# beamshutter.net
KiCad netlist of a schematic drawn in EAGLE
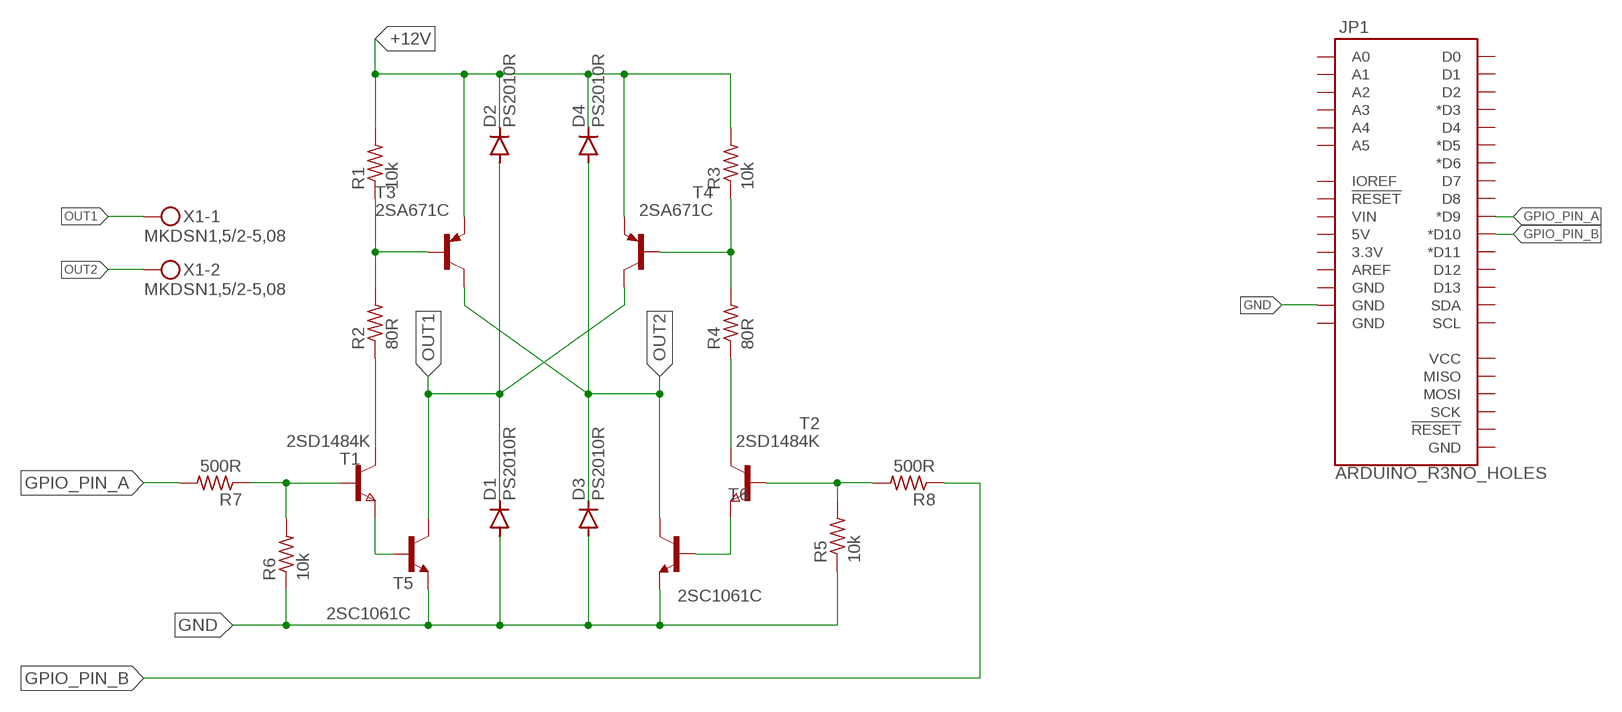
[diagram p0: schematic, sheet 1]

(export (version "E")
  (design (tool "Eeschema 10.0.6"))
  (components
    (comp (ref "D1")
      (value "PS2010R")
      (footprint "eagle-import:DO15-12")
      (libsource (lib "eagle-import") (part "RGP15"))
    )
    (comp (ref "D2")
      (value "PS2010R")
      (footprint "eagle-import:DO15-12")
      (libsource (lib "eagle-import") (part "RGP15"))
    )
    (comp (ref "D3")
      (value "PS2010R")
      (footprint "eagle-import:DO15-12")
      (libsource (lib "eagle-import") (part "RGP15"))
    )
    (comp (ref "D4")
      (value "PS2010R")
      (footprint "eagle-import:DO15-12")
      (libsource (lib "eagle-import") (part "RGP15"))
    )
    (comp (ref "JP1")
      (value "ARDUINO_R3NO_HOLES")
      (footprint "eagle-import:ARDUINO_R3_NO_HOLES")
      (libsource (lib "eagle-import") (part "ARDUINO_R3NO_HOLES"))
    )
    (comp (ref "R1")
      (value "10k")
      (footprint "eagle-import:2012-R")
      (libsource (lib "eagle-import") (part "R-2012"))
    )
    (comp (ref "R2")
      (value "80R")
      (footprint "eagle-import:2012-R")
      (libsource (lib "eagle-import") (part "R-2012"))
    )
    (comp (ref "R3")
      (value "10k")
      (footprint "eagle-import:2012-R")
      (libsource (lib "eagle-import") (part "R-2012"))
    )
    (comp (ref "R4")
      (value "80R")
      (footprint "eagle-import:2012-R")
      (libsource (lib "eagle-import") (part "R-2012"))
    )
    (comp (ref "R5")
      (value "10k")
      (footprint "eagle-import:2012-R")
      (libsource (lib "eagle-import") (part "R-2012"))
    )
    (comp (ref "R6")
      (value "10k")
      (footprint "eagle-import:2012-R")
      (libsource (lib "eagle-import") (part "R-2012"))
    )
    (comp (ref "R7")
      (value "500R")
      (footprint "eagle-import:2012-R")
      (libsource (lib "eagle-import") (part "R-2012"))
    )
    (comp (ref "R8")
      (value "500R")
      (footprint "eagle-import:2012-R")
      (libsource (lib "eagle-import") (part "R-2012"))
    )
    (comp (ref "T1")
      (value "2SD1484K")
      (footprint "eagle-import:SOT323")
      (fields (field (name "MPN") "DSS4160U-7"))
      (libsource (lib "eagle-import") (part "NPNSOT323"))
    )
    (comp (ref "T2")
      (value "2SD1484K")
      (footprint "eagle-import:SOT323")
      (fields (field (name "MPN") "DSS4160U-7"))
      (libsource (lib "eagle-import") (part "NPNSOT323"))
    )
    (comp (ref "T3")
      (value "2SA671C")
      (footprint "eagle-import:TO220V")
      (libsource (lib "eagle-import") (part "-PNP-TO220V"))
    )
    (comp (ref "T4")
      (value "2SA671C")
      (footprint "eagle-import:TO220V")
      (libsource (lib "eagle-import") (part "-PNP-TO220V"))
    )
    (comp (ref "T5")
      (value "2SC1061C")
      (footprint "eagle-import:TO220V")
      (libsource (lib "eagle-import") (part "-NPN-TO220V"))
    )
    (comp (ref "T6")
      (value "2SC1061C")
      (footprint "eagle-import:TO220V")
      (libsource (lib "eagle-import") (part "-NPN-TO220V"))
    )
    (comp (ref "X1")
      (value "MKDSN1,5/2-5,08")
      (footprint "eagle-import:MKDSN1,5_2-5,08")
      (libsource (lib "eagle-import") (part "MKDSN1,5/2-5,08"))
    )
  )
  (nets
    (net (code "1") (name "+12V") (class "Default")
      (node (ref "D2") (pin "C") (pinfunction "C_C") (pintype "passive"))
      (node (ref "D4") (pin "C") (pinfunction "C_C") (pintype "passive"))
      (node (ref "R1") (pin "2") (pinfunction "2_2") (pintype "passive"))
      (node (ref "R3") (pin "2") (pinfunction "2_2") (pintype "passive"))
      (node (ref "T3") (pin "3") (pinfunction "E_3") (pintype "passive"))
      (node (ref "T4") (pin "3") (pinfunction "E_3") (pintype "passive"))
    )
    (net (code "2") (name "GND") (class "Default")
      (node (ref "D1") (pin "A") (pinfunction "A_A") (pintype "passive"))
      (node (ref "D3") (pin "A") (pinfunction "A_A") (pintype "passive"))
      (node (ref "JP1") (pin "GND@3") (pinfunction "GND_GND@3") (pintype "bidirectional"))
      (node (ref "R5") (pin "1") (pinfunction "1_1") (pintype "passive"))
      (node (ref "R6") (pin "1") (pinfunction "1_1") (pintype "passive"))
      (node (ref "T5") (pin "3") (pinfunction "E_3") (pintype "passive"))
      (node (ref "T6") (pin "3") (pinfunction "E_3") (pintype "passive"))
    )
    (net (code "3") (name "GPIO_PIN_A") (class "Default")
      (node (ref "JP1") (pin "D9") (pinfunction "*D9_D9") (pintype "bidirectional"))
      (node (ref "R7") (pin "2") (pinfunction "2_2") (pintype "passive"))
    )
    (net (code "4") (name "GPIO_PIN_B") (class "Default")
      (node (ref "JP1") (pin "D10") (pinfunction "*D10_D10") (pintype "bidirectional"))
      (node (ref "R8") (pin "1") (pinfunction "1_1") (pintype "passive"))
    )
    (net (code "5") (name "Net-(T1-B)") (class "Default")
      (node (ref "R6") (pin "2") (pinfunction "2_2") (pintype "passive"))
      (node (ref "R7") (pin "1") (pinfunction "1_1") (pintype "passive"))
      (node (ref "T1") (pin "2") (pinfunction "B_2") (pintype "passive"))
    )
    (net (code "6") (name "Net-(T1-C)") (class "Default")
      (node (ref "R2") (pin "1") (pinfunction "1_1") (pintype "passive"))
      (node (ref "T1") (pin "1") (pinfunction "C_1") (pintype "passive"))
    )
    (net (code "7") (name "Net-(T1-E)") (class "Default")
      (node (ref "T1") (pin "3") (pinfunction "E_3") (pintype "passive"))
      (node (ref "T5") (pin "1") (pinfunction "B_1") (pintype "passive"))
    )
    (net (code "8") (name "Net-(T2-B)") (class "Default")
      (node (ref "R5") (pin "2") (pinfunction "2_2") (pintype "passive"))
      (node (ref "R8") (pin "2") (pinfunction "2_2") (pintype "passive"))
      (node (ref "T2") (pin "2") (pinfunction "B_2") (pintype "passive"))
    )
    (net (code "9") (name "Net-(T2-C)") (class "Default")
      (node (ref "R4") (pin "1") (pinfunction "1_1") (pintype "passive"))
      (node (ref "T2") (pin "1") (pinfunction "C_1") (pintype "passive"))
    )
    (net (code "10") (name "Net-(T2-E)") (class "Default")
      (node (ref "T2") (pin "3") (pinfunction "E_3") (pintype "passive"))
      (node (ref "T6") (pin "1") (pinfunction "B_1") (pintype "passive"))
    )
    (net (code "11") (name "Net-(T3-B)") (class "Default")
      (node (ref "R1") (pin "1") (pinfunction "1_1") (pintype "passive"))
      (node (ref "R2") (pin "2") (pinfunction "2_2") (pintype "passive"))
      (node (ref "T3") (pin "1") (pinfunction "B_1") (pintype "passive"))
    )
    (net (code "12") (name "Net-(T4-B)") (class "Default")
      (node (ref "R3") (pin "1") (pinfunction "1_1") (pintype "passive"))
      (node (ref "R4") (pin "2") (pinfunction "2_2") (pintype "passive"))
      (node (ref "T4") (pin "1") (pinfunction "B_1") (pintype "passive"))
    )
    (net (code "13") (name "OUT1") (class "Default")
      (node (ref "D1") (pin "C") (pinfunction "C_C") (pintype "passive"))
      (node (ref "D2") (pin "A") (pinfunction "A_A") (pintype "passive"))
      (node (ref "T4") (pin "2") (pinfunction "C_2") (pintype "passive"))
      (node (ref "T5") (pin "2") (pinfunction "C_2") (pintype "passive"))
      (node (ref "X1") (pin "1") (pinfunction "KL_1") (pintype "passive"))
    )
    (net (code "14") (name "OUT2") (class "Default")
      (node (ref "D3") (pin "C") (pinfunction "C_C") (pintype "passive"))
      (node (ref "D4") (pin "A") (pinfunction "A_A") (pintype "passive"))
      (node (ref "T3") (pin "2") (pinfunction "C_2") (pintype "passive"))
      (node (ref "T6") (pin "2") (pinfunction "C_2") (pintype "passive"))
      (node (ref "X1") (pin "2") (pinfunction "KL_2") (pintype "passive"))
    )
    (net (code "15") (name "unconnected-(JP1-*D3-PadD3)") (class "Default")
      (node (ref "JP1") (pin "D3") (pinfunction "*D3_D3") (pintype "bidirectional"))
    )
    (net (code "16") (name "unconnected-(JP1-*D5-PadD5)") (class "Default")
      (node (ref "JP1") (pin "D5") (pinfunction "*D5_D5") (pintype "bidirectional"))
    )
    (net (code "17") (name "unconnected-(JP1-*D6-PadD6)") (class "Default")
      (node (ref "JP1") (pin "D6") (pinfunction "*D6_D6") (pintype "bidirectional"))
    )
    (net (code "18") (name "unconnected-(JP1-*D11-PadD11)") (class "Default")
      (node (ref "JP1") (pin "D11") (pinfunction "*D11_D11") (pintype "bidirectional"))
    )
    (net (code "19") (name "unconnected-(JP1-GND-PadGND@1)") (class "Default")
      (node (ref "JP1") (pin "GND@1") (pinfunction "GND_GND@1") (pintype "bidirectional"))
    )
    (net (code "20") (name "unconnected-(JP1-GND-PadGND@2)") (class "Default")
      (node (ref "JP1") (pin "GND@2") (pinfunction "GND_GND@2") (pintype "bidirectional"))
    )
    (net (code "21") (name "unconnected-(JP1-GND-PadGND@4)") (class "Default")
      (node (ref "JP1") (pin "GND@4") (pinfunction "GND_GND@4") (pintype "bidirectional"))
    )
    (net (code "22") (name "unconnected-(JP1-Pad3.3V)") (class "Default")
      (node (ref "JP1") (pin "3.3V") (pinfunction "3.3V_3.3V") (pintype "bidirectional"))
    )
    (net (code "23") (name "unconnected-(JP1-Pad5V)") (class "Default")
      (node (ref "JP1") (pin "5V") (pinfunction "5V_5V") (pintype "bidirectional"))
    )
    (net (code "24") (name "unconnected-(JP1-PadA0)") (class "Default")
      (node (ref "JP1") (pin "A0") (pinfunction "A0_A0") (pintype "bidirectional"))
    )
    (net (code "25") (name "unconnected-(JP1-PadA1)") (class "Default")
      (node (ref "JP1") (pin "A1") (pinfunction "A1_A1") (pintype "bidirectional"))
    )
    (net (code "26") (name "unconnected-(JP1-PadA2)") (class "Default")
      (node (ref "JP1") (pin "A2") (pinfunction "A2_A2") (pintype "bidirectional"))
    )
    (net (code "27") (name "unconnected-(JP1-PadA3)") (class "Default")
      (node (ref "JP1") (pin "A3") (pinfunction "A3_A3") (pintype "bidirectional"))
    )
    (net (code "28") (name "unconnected-(JP1-PadA4)") (class "Default")
      (node (ref "JP1") (pin "A4") (pinfunction "A4_A4") (pintype "bidirectional"))
    )
    (net (code "29") (name "unconnected-(JP1-PadA5)") (class "Default")
      (node (ref "JP1") (pin "A5") (pinfunction "A5_A5") (pintype "bidirectional"))
    )
    (net (code "30") (name "unconnected-(JP1-PadAREF)") (class "Default")
      (node (ref "JP1") (pin "AREF") (pinfunction "AREF_AREF") (pintype "bidirectional"))
    )
    (net (code "31") (name "unconnected-(JP1-PadD0)") (class "Default")
      (node (ref "JP1") (pin "D0") (pinfunction "D0_D0") (pintype "bidirectional"))
    )
    (net (code "32") (name "unconnected-(JP1-PadD1)") (class "Default")
      (node (ref "JP1") (pin "D1") (pinfunction "D1_D1") (pintype "bidirectional"))
    )
    (net (code "33") (name "unconnected-(JP1-PadD2)") (class "Default")
      (node (ref "JP1") (pin "D2") (pinfunction "D2_D2") (pintype "bidirectional"))
    )
    (net (code "34") (name "unconnected-(JP1-PadD4)") (class "Default")
      (node (ref "JP1") (pin "D4") (pinfunction "D4_D4") (pintype "bidirectional"))
    )
    (net (code "35") (name "unconnected-(JP1-PadD7)") (class "Default")
      (node (ref "JP1") (pin "D7") (pinfunction "D7_D7") (pintype "bidirectional"))
    )
    (net (code "36") (name "unconnected-(JP1-PadD8)") (class "Default")
      (node (ref "JP1") (pin "D8") (pinfunction "D8_D8") (pintype "bidirectional"))
    )
    (net (code "37") (name "unconnected-(JP1-PadD12)") (class "Default")
      (node (ref "JP1") (pin "D12") (pinfunction "D12_D12") (pintype "bidirectional"))
    )
    (net (code "38") (name "unconnected-(JP1-PadD13)") (class "Default")
      (node (ref "JP1") (pin "D13") (pinfunction "D13_D13") (pintype "bidirectional"))
    )
    (net (code "39") (name "unconnected-(JP1-PadIOREF)") (class "Default")
      (node (ref "JP1") (pin "IOREF") (pinfunction "IOREF_IOREF") (pintype "bidirectional"))
    )
    (net (code "40") (name "unconnected-(JP1-PadMISO)") (class "Default")
      (node (ref "JP1") (pin "MISO") (pinfunction "MISO_MISO") (pintype "bidirectional"))
    )
    (net (code "41") (name "unconnected-(JP1-PadMOSI)") (class "Default")
      (node (ref "JP1") (pin "MOSI") (pinfunction "MOSI_MOSI") (pintype "bidirectional"))
    )
    (net (code "42") (name "unconnected-(JP1-PadSCK)") (class "Default")
      (node (ref "JP1") (pin "SCK") (pinfunction "SCK_SCK") (pintype "bidirectional"))
    )
    (net (code "43") (name "unconnected-(JP1-PadSCL)") (class "Default")
      (node (ref "JP1") (pin "SCL") (pinfunction "SCL_SCL") (pintype "bidirectional"))
    )
    (net (code "44") (name "unconnected-(JP1-PadSDA)") (class "Default")
      (node (ref "JP1") (pin "SDA") (pinfunction "SDA_SDA") (pintype "bidirectional"))
    )
    (net (code "45") (name "unconnected-(JP1-PadVCC)") (class "Default")
      (node (ref "JP1") (pin "VCC") (pinfunction "VCC_VCC") (pintype "bidirectional"))
    )
    (net (code "46") (name "unconnected-(JP1-PadVIN)") (class "Default")
      (node (ref "JP1") (pin "VIN") (pinfunction "VIN_VIN") (pintype "bidirectional"))
    )
    (net (code "47") (name "unconnected-(JP1-~{RESET}-PadRESET@1)") (class "Default")
      (node (ref "JP1") (pin "RESET@1") (pinfunction "~{RESET}_RESET@1") (pintype "bidirectional"))
    )
    (net (code "48") (name "unconnected-(JP1-~{RESET}-PadRESET@2)") (class "Default")
      (node (ref "JP1") (pin "RESET@2") (pinfunction "~{RESET}_RESET@2") (pintype "bidirectional"))
    )
  )
)
